# sram.net
KiCad netlist of a schematic drawn in Altium Designer
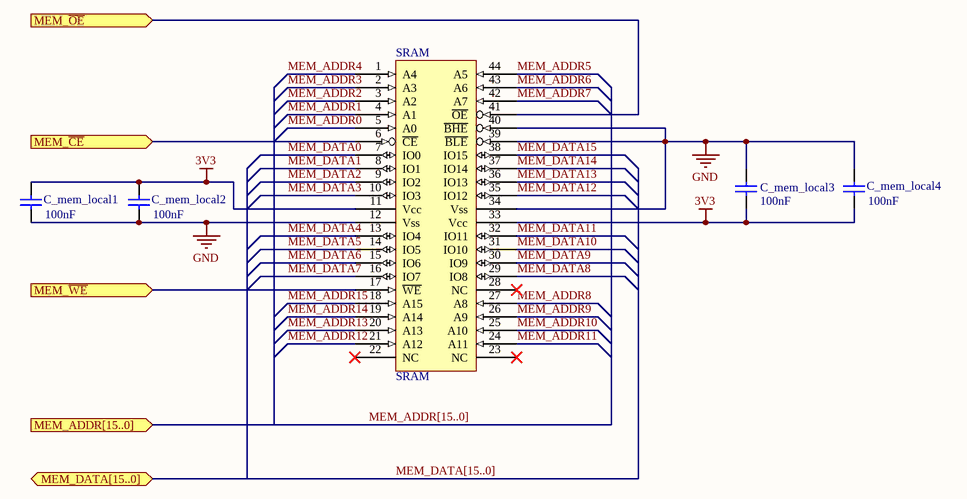
[diagram p0: sram.SchDoc]

(export (version "E")
  (design (tool "Eeschema 10.0.6"))
  (components
    (comp (ref "C_mem_local1")
      (value "100nF")
      (footprint "ourprints:0805")
      (description "Capacitor (Semiconductor SIM Model)")
      (fields (field (name "Comment") "Cap Semi") (field (name "PUBLISHER") "Altium Limited"))
      (libsource (lib "Miscellaneous Devices") (part "Cap Semi"))
    )
    (comp (ref "C_mem_local2")
      (value "100nF")
      (footprint "ourprints:0805")
      (description "Capacitor (Semiconductor SIM Model)")
      (fields (field (name "Comment") "Cap Semi") (field (name "PUBLISHER") "Altium Limited"))
      (libsource (lib "Miscellaneous Devices") (part "Cap Semi"))
    )
    (comp (ref "C_mem_local3")
      (value "100nF")
      (footprint "ourprints:0805")
      (description "Capacitor (Semiconductor SIM Model)")
      (fields (field (name "Comment") "Cap Semi") (field (name "PUBLISHER") "Altium Limited"))
      (libsource (lib "Miscellaneous Devices") (part "Cap Semi"))
    )
    (comp (ref "C_mem_local4")
      (value "100nF")
      (footprint "ourprints:0805")
      (description "Capacitor (Semiconductor SIM Model)")
      (fields (field (name "Comment") "Cap Semi") (field (name "PUBLISHER") "Altium Limited"))
      (libsource (lib "Miscellaneous Devices") (part "Cap Semi"))
    )
    (comp (ref "SRAM") (value "SRAM") (footprint "TSOP44") (libsource (lib "ourlibs") (part "SRAM")))
  )
  (nets
    (net (code "1") (name "/MEM_ADDR0") (class "Default")
      (node (ref "SRAM") (pin "5") (pinfunction "A0_5") (pintype "input"))
    )
    (net (code "2") (name "/MEM_ADDR1") (class "Default")
      (node (ref "SRAM") (pin "4") (pinfunction "A1_4") (pintype "input"))
    )
    (net (code "3") (name "/MEM_ADDR2") (class "Default")
      (node (ref "SRAM") (pin "3") (pinfunction "A2_3") (pintype "input"))
    )
    (net (code "4") (name "/MEM_ADDR3") (class "Default")
      (node (ref "SRAM") (pin "2") (pinfunction "A3_2") (pintype "input"))
    )
    (net (code "5") (name "/MEM_ADDR4") (class "Default")
      (node (ref "SRAM") (pin "1") (pinfunction "A4_1") (pintype "input"))
    )
    (net (code "6") (name "/MEM_ADDR5") (class "Default")
      (node (ref "SRAM") (pin "44") (pinfunction "A5_44") (pintype "input"))
    )
    (net (code "7") (name "/MEM_ADDR6") (class "Default")
      (node (ref "SRAM") (pin "43") (pinfunction "A6_43") (pintype "input"))
    )
    (net (code "8") (name "/MEM_ADDR7") (class "Default")
      (node (ref "SRAM") (pin "42") (pinfunction "A7_42") (pintype "input"))
    )
    (net (code "9") (name "/MEM_ADDR8") (class "Default")
      (node (ref "SRAM") (pin "27") (pinfunction "A8_27") (pintype "input"))
    )
    (net (code "10") (name "/MEM_ADDR9") (class "Default")
      (node (ref "SRAM") (pin "26") (pinfunction "A9_26") (pintype "input"))
    )
    (net (code "11") (name "/MEM_ADDR10") (class "Default")
      (node (ref "SRAM") (pin "25") (pinfunction "A10_25") (pintype "input"))
    )
    (net (code "12") (name "/MEM_ADDR11") (class "Default")
      (node (ref "SRAM") (pin "24") (pinfunction "A11_24") (pintype "input"))
    )
    (net (code "13") (name "/MEM_ADDR12") (class "Default")
      (node (ref "SRAM") (pin "21") (pinfunction "A12_21") (pintype "input"))
    )
    (net (code "14") (name "/MEM_ADDR13") (class "Default")
      (node (ref "SRAM") (pin "20") (pinfunction "A13_20") (pintype "input"))
    )
    (net (code "15") (name "/MEM_ADDR14") (class "Default")
      (node (ref "SRAM") (pin "19") (pinfunction "A14_19") (pintype "input"))
    )
    (net (code "16") (name "/MEM_ADDR15") (class "Default")
      (node (ref "SRAM") (pin "18") (pinfunction "A15_18") (pintype "input"))
    )
    (net (code "18") (name "/MEM_DATA0") (class "Default")
      (node (ref "SRAM") (pin "7") (pinfunction "IO0_7") (pintype "bidirectional"))
    )
    (net (code "19") (name "/MEM_DATA1") (class "Default")
      (node (ref "SRAM") (pin "8") (pinfunction "IO1_8") (pintype "bidirectional"))
    )
    (net (code "20") (name "/MEM_DATA2") (class "Default")
      (node (ref "SRAM") (pin "9") (pinfunction "IO2_9") (pintype "bidirectional"))
    )
    (net (code "21") (name "/MEM_DATA3") (class "Default")
      (node (ref "SRAM") (pin "10") (pinfunction "IO3_10") (pintype "bidirectional"))
    )
    (net (code "22") (name "/MEM_DATA4") (class "Default")
      (node (ref "SRAM") (pin "13") (pinfunction "IO4_13") (pintype "bidirectional"))
    )
    (net (code "23") (name "/MEM_DATA5") (class "Default")
      (node (ref "SRAM") (pin "14") (pinfunction "IO5_14") (pintype "bidirectional"))
    )
    (net (code "24") (name "/MEM_DATA6") (class "Default")
      (node (ref "SRAM") (pin "15") (pinfunction "IO6_15") (pintype "bidirectional"))
    )
    (net (code "25") (name "/MEM_DATA7") (class "Default")
      (node (ref "SRAM") (pin "16") (pinfunction "IO7_16") (pintype "bidirectional"))
    )
    (net (code "26") (name "/MEM_DATA8") (class "Default")
      (node (ref "SRAM") (pin "29") (pinfunction "IO8_29") (pintype "bidirectional"))
    )
    (net (code "27") (name "/MEM_DATA9") (class "Default")
      (node (ref "SRAM") (pin "30") (pinfunction "IO9_30") (pintype "bidirectional"))
    )
    (net (code "28") (name "/MEM_DATA10") (class "Default")
      (node (ref "SRAM") (pin "31") (pinfunction "IO10_31") (pintype "bidirectional"))
    )
    (net (code "29") (name "/MEM_DATA11") (class "Default")
      (node (ref "SRAM") (pin "32") (pinfunction "IO11_32") (pintype "bidirectional"))
    )
    (net (code "30") (name "/MEM_DATA12") (class "Default")
      (node (ref "SRAM") (pin "35") (pinfunction "IO12_35") (pintype "bidirectional"))
    )
    (net (code "31") (name "/MEM_DATA13") (class "Default")
      (node (ref "SRAM") (pin "36") (pinfunction "IO13_36") (pintype "bidirectional"))
    )
    (net (code "32") (name "/MEM_DATA14") (class "Default")
      (node (ref "SRAM") (pin "37") (pinfunction "IO14_37") (pintype "bidirectional"))
    )
    (net (code "33") (name "/MEM_DATA15") (class "Default")
      (node (ref "SRAM") (pin "38") (pinfunction "IO15_38") (pintype "bidirectional"))
    )
    (net (code "35") (name "/MEM_~{CE}") (class "Default")
      (node (ref "SRAM") (pin "6") (pinfunction "~{CE}_6") (pintype "input"))
    )
    (net (code "36") (name "/MEM_~{OE}") (class "Default")
      (node (ref "SRAM") (pin "41") (pinfunction "~{OE}_41") (pintype "input"))
    )
    (net (code "37") (name "/MEM_~{WE}") (class "Default")
      (node (ref "SRAM") (pin "17") (pinfunction "~{WE}_17") (pintype "input"))
    )
    (net (code "38") (name "3V3") (class "Default")
      (node (ref "C_mem_local1") (pin "2") (pinfunction "2_2") (pintype "passive"))
      (node (ref "C_mem_local2") (pin "2") (pinfunction "2_2") (pintype "passive"))
      (node (ref "C_mem_local3") (pin "1") (pinfunction "1_1") (pintype "passive"))
      (node (ref "C_mem_local4") (pin "1") (pinfunction "1_1") (pintype "passive"))
      (node (ref "SRAM") (pin "11") (pinfunction "Vcc_11") (pintype "power_in"))
      (node (ref "SRAM") (pin "33") (pinfunction "Vcc_33") (pintype "power_in"))
    )
    (net (code "39") (name "GND") (class "Default")
      (node (ref "C_mem_local1") (pin "1") (pinfunction "1_1") (pintype "passive"))
      (node (ref "C_mem_local2") (pin "1") (pinfunction "1_1") (pintype "passive"))
      (node (ref "C_mem_local3") (pin "2") (pinfunction "2_2") (pintype "passive"))
      (node (ref "C_mem_local4") (pin "2") (pinfunction "2_2") (pintype "passive"))
      (node (ref "SRAM") (pin "12") (pinfunction "Vss_12") (pintype "power_in"))
      (node (ref "SRAM") (pin "34") (pinfunction "Vss_34") (pintype "power_in"))
      (node (ref "SRAM") (pin "39") (pinfunction "~{BLE}_39") (pintype "input"))
      (node (ref "SRAM") (pin "40") (pinfunction "~{BHE}_40") (pintype "input"))
    )
    (net (code "40") (name "unconnected-(SRAM-NC-Pad22)") (class "Default")
      (node (ref "SRAM") (pin "22") (pinfunction "NC_22") (pintype "passive+no_connect"))
    )
    (net (code "41") (name "unconnected-(SRAM-NC-Pad23)") (class "Default")
      (node (ref "SRAM") (pin "23") (pinfunction "NC_23") (pintype "passive+no_connect"))
    )
    (net (code "42") (name "unconnected-(SRAM-NC-Pad28)") (class "Default")
      (node (ref "SRAM") (pin "28") (pinfunction "NC_28") (pintype "passive+no_connect"))
    )
  )
)
